# IDC_EXT_Connectors.net
KiCad netlist of a schematic drawn in Altium Designer
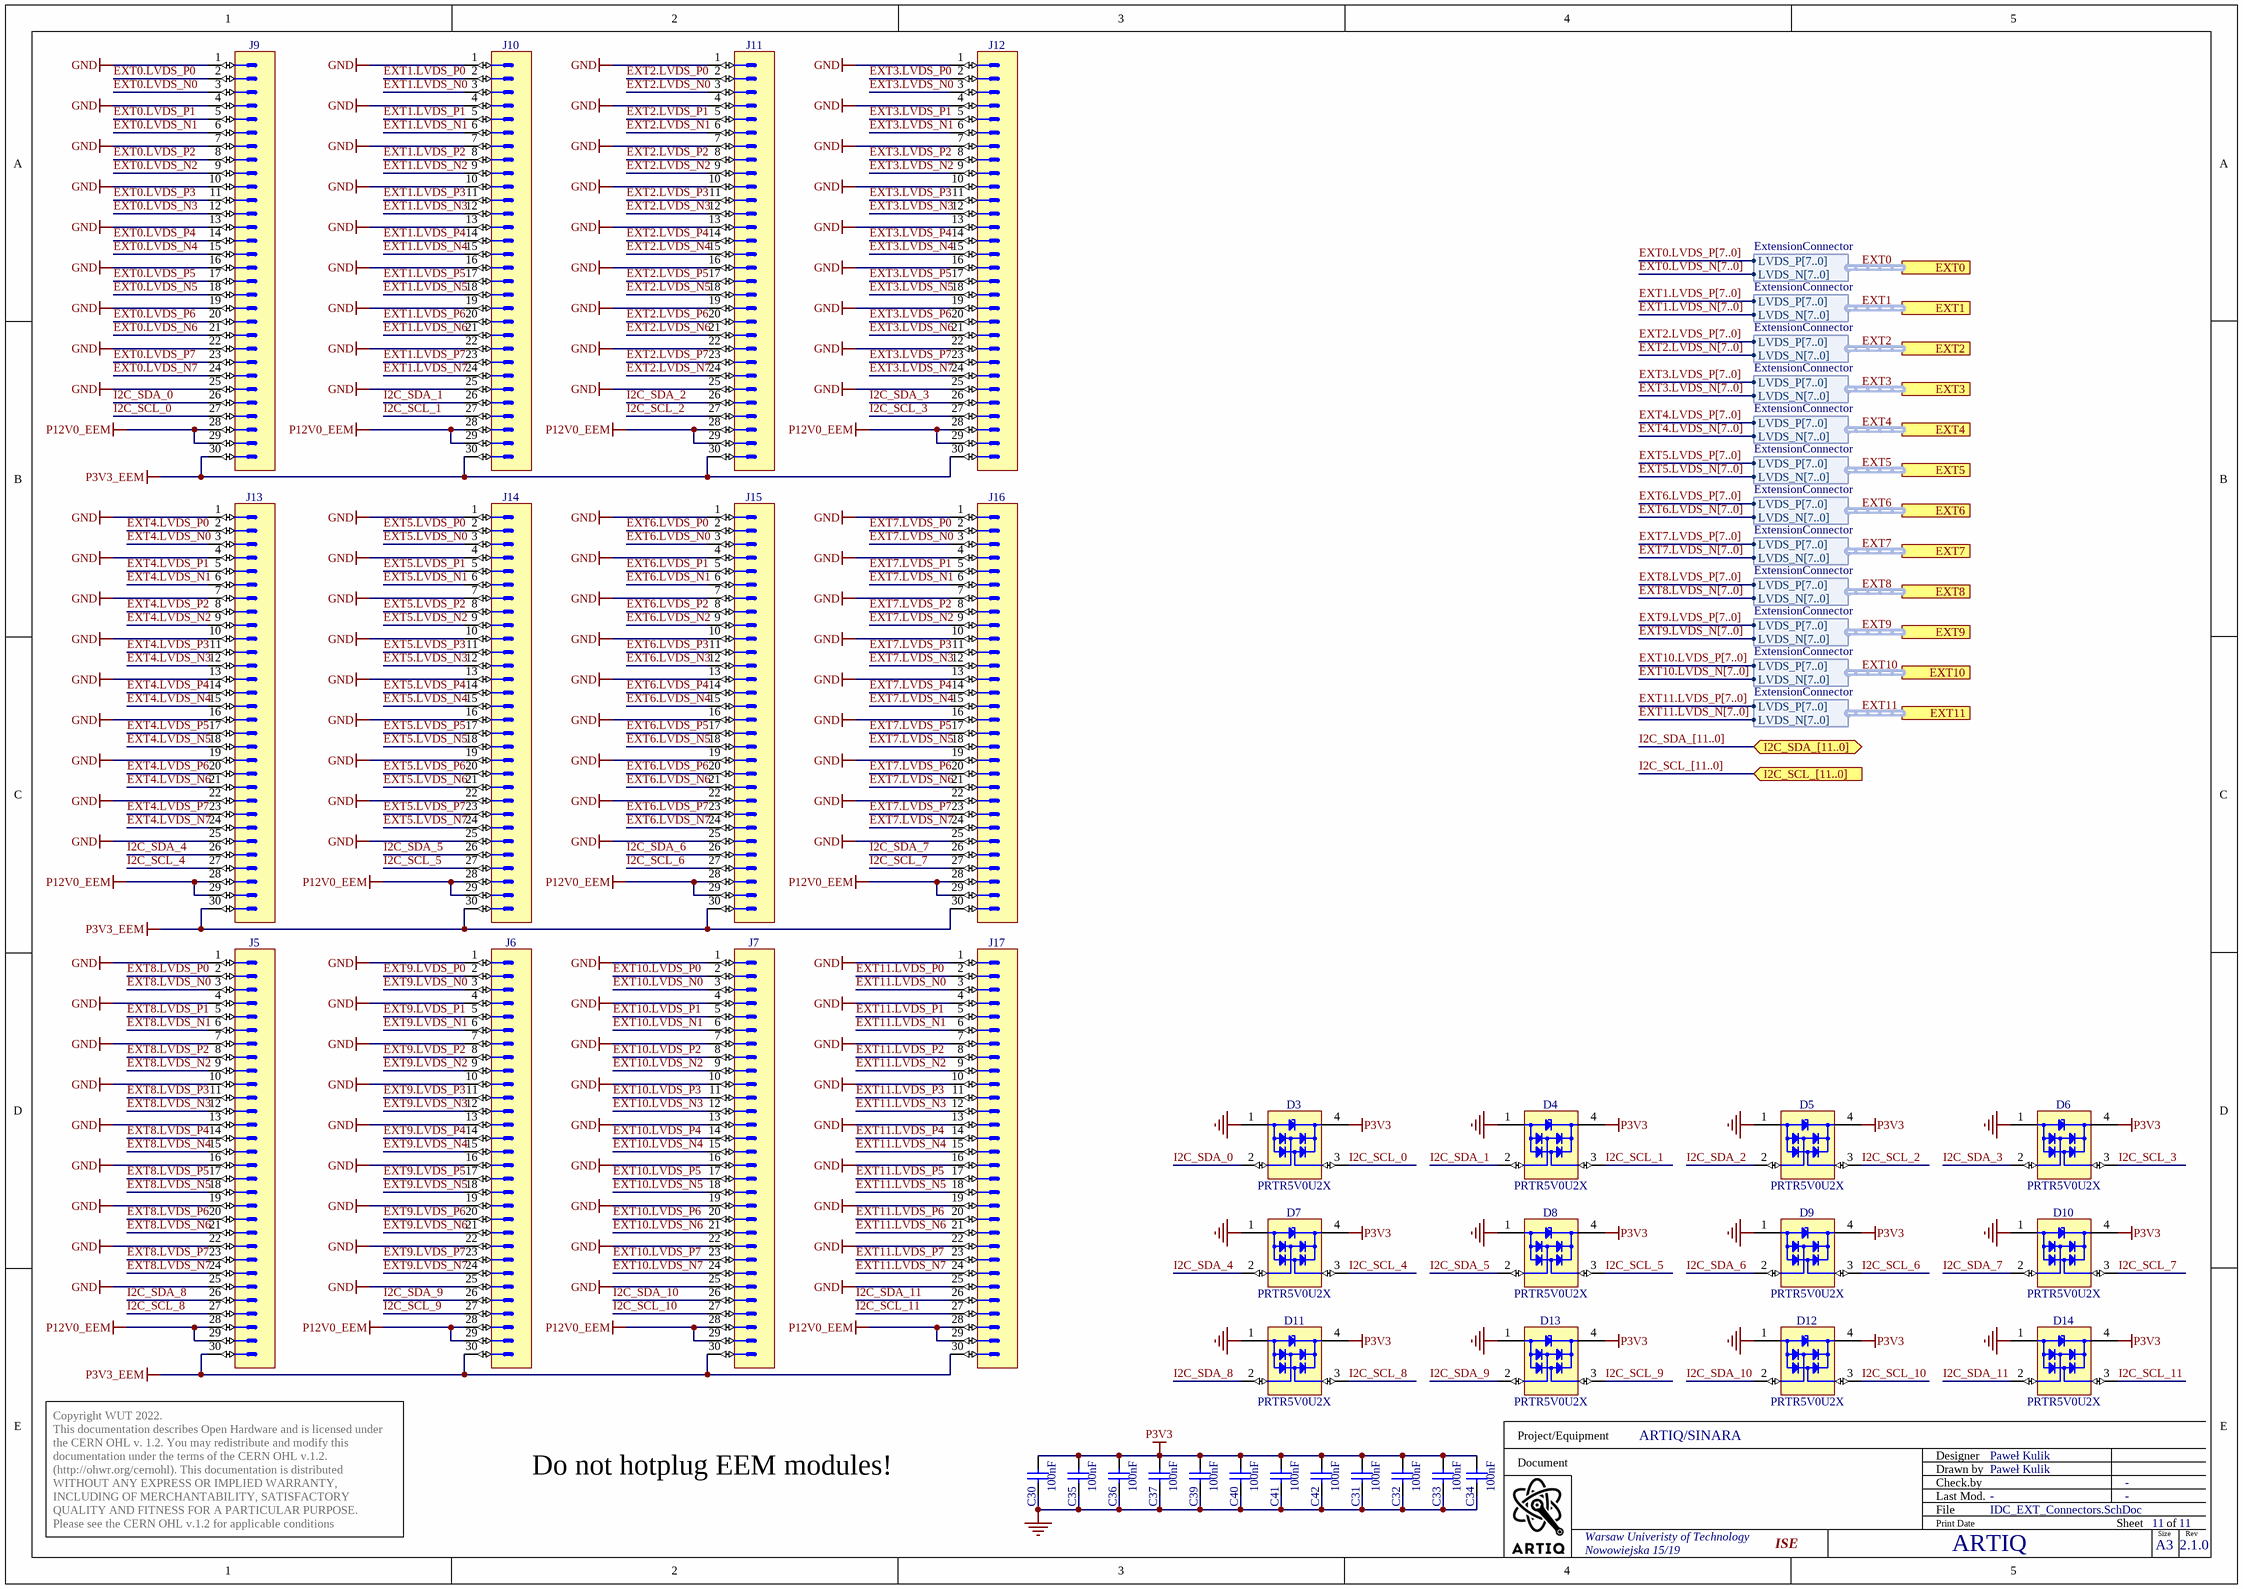
[diagram p0: IDC_EXT_Connectors.SchDoc]

(export (version "E")
  (design (tool "Eeschema 10.0.6"))
  (components
    (comp (ref "C30")
      (value "100nF")
      (footprint "CAPC0603X33N")
      (description "Non-polarised capacitor")
      (fields
        (field (name "PART NUMBER") "CC0201_100NF_6.3V_10%_X5R")
        (field (name "VOLTAGE") "6.3V")
        (field (name "AUTHOR") "CERN DEM JLC")
      )
      (libsource (lib "Capacitors") (part "Capacitor - non polarized"))
    )
    (comp (ref "C31")
      (value "100nF")
      (footprint "CAPC0603X33N")
      (description "Non-polarised capacitor")
      (fields
        (field (name "PART NUMBER") "CC0201_100NF_6.3V_10%_X5R")
        (field (name "VOLTAGE") "6.3V")
        (field (name "AUTHOR") "CERN DEM JLC")
      )
      (libsource (lib "Capacitors") (part "Capacitor - non polarized"))
    )
    (comp (ref "C32")
      (value "100nF")
      (footprint "CAPC0603X33N")
      (description "Non-polarised capacitor")
      (fields
        (field (name "PART NUMBER") "CC0201_100NF_6.3V_10%_X5R")
        (field (name "VOLTAGE") "6.3V")
        (field (name "AUTHOR") "CERN DEM JLC")
      )
      (libsource (lib "Capacitors") (part "Capacitor - non polarized"))
    )
    (comp (ref "C33")
      (value "100nF")
      (footprint "CAPC0603X33N")
      (description "Non-polarised capacitor")
      (fields
        (field (name "PART NUMBER") "CC0201_100NF_6.3V_10%_X5R")
        (field (name "VOLTAGE") "6.3V")
        (field (name "AUTHOR") "CERN DEM JLC")
      )
      (libsource (lib "Capacitors") (part "Capacitor - non polarized"))
    )
    (comp (ref "C34")
      (value "100nF")
      (footprint "CAPC0603X33N")
      (description "Non-polarised capacitor")
      (fields
        (field (name "PART NUMBER") "CC0201_100NF_6.3V_10%_X5R")
        (field (name "VOLTAGE") "6.3V")
        (field (name "AUTHOR") "CERN DEM JLC")
      )
      (libsource (lib "Capacitors") (part "Capacitor - non polarized"))
    )
    (comp (ref "C35")
      (value "100nF")
      (footprint "CAPC0603X33N")
      (description "Non-polarised capacitor")
      (fields
        (field (name "PART NUMBER") "CC0201_100NF_6.3V_10%_X5R")
        (field (name "VOLTAGE") "6.3V")
        (field (name "AUTHOR") "CERN DEM JLC")
      )
      (libsource (lib "Capacitors") (part "Capacitor - non polarized"))
    )
    (comp (ref "C36")
      (value "100nF")
      (footprint "CAPC0603X33N")
      (description "Non-polarised capacitor")
      (fields
        (field (name "PART NUMBER") "CC0201_100NF_6.3V_10%_X5R")
        (field (name "VOLTAGE") "6.3V")
        (field (name "AUTHOR") "CERN DEM JLC")
      )
      (libsource (lib "Capacitors") (part "Capacitor - non polarized"))
    )
    (comp (ref "C37")
      (value "100nF")
      (footprint "CAPC0603X33N")
      (description "Non-polarised capacitor")
      (fields
        (field (name "PART NUMBER") "CC0201_100NF_6.3V_10%_X5R")
        (field (name "VOLTAGE") "6.3V")
        (field (name "AUTHOR") "CERN DEM JLC")
      )
      (libsource (lib "Capacitors") (part "Capacitor - non polarized"))
    )
    (comp (ref "C39")
      (value "100nF")
      (footprint "CAPC0603X33N")
      (description "Non-polarised capacitor")
      (fields
        (field (name "PART NUMBER") "CC0201_100NF_6.3V_10%_X5R")
        (field (name "VOLTAGE") "6.3V")
        (field (name "AUTHOR") "CERN DEM JLC")
      )
      (libsource (lib "Capacitors") (part "Capacitor - non polarized"))
    )
    (comp (ref "C40")
      (value "100nF")
      (footprint "CAPC0603X33N")
      (description "Non-polarised capacitor")
      (fields
        (field (name "PART NUMBER") "CC0201_100NF_6.3V_10%_X5R")
        (field (name "VOLTAGE") "6.3V")
        (field (name "AUTHOR") "CERN DEM JLC")
      )
      (libsource (lib "Capacitors") (part "Capacitor - non polarized"))
    )
    (comp (ref "C41")
      (value "100nF")
      (footprint "CAPC0603X33N")
      (description "Non-polarised capacitor")
      (fields
        (field (name "PART NUMBER") "CC0201_100NF_6.3V_10%_X5R")
        (field (name "VOLTAGE") "6.3V")
        (field (name "AUTHOR") "CERN DEM JLC")
      )
      (libsource (lib "Capacitors") (part "Capacitor - non polarized"))
    )
    (comp (ref "C42")
      (value "100nF")
      (footprint "CAPC0603X33N")
      (description "Non-polarised capacitor")
      (fields
        (field (name "PART NUMBER") "CC0201_100NF_6.3V_10%_X5R")
        (field (name "VOLTAGE") "6.3V")
        (field (name "AUTHOR") "CERN DEM JLC")
      )
      (libsource (lib "Capacitors") (part "Capacitor - non polarized"))
    )
    (comp (ref "D3")
      (value "PRTR5V0U2X")
      (footprint "SOT190P230X110-4N")
      (description "Ultra Low Capacitance Double Rail-to-Rail ESD Protection Diode")
      (fields
        (field (name "VOLTAGE") "5.5V")
        (field (name "MANUFACTURER") "NXP SEMICONDUCTORS")
        (field (name "AUTHOR") "CERN DEM JLC")
      )
      (libsource (lib "ICs And Semiconductors") (part "PRTR5V0U2X"))
    )
    (comp (ref "D4")
      (value "PRTR5V0U2X")
      (footprint "SOT190P230X110-4N")
      (description "Ultra Low Capacitance Double Rail-to-Rail ESD Protection Diode")
      (fields
        (field (name "VOLTAGE") "5.5V")
        (field (name "MANUFACTURER") "NXP SEMICONDUCTORS")
        (field (name "AUTHOR") "CERN DEM JLC")
      )
      (libsource (lib "ICs And Semiconductors") (part "PRTR5V0U2X"))
    )
    (comp (ref "D5")
      (value "PRTR5V0U2X")
      (footprint "SOT190P230X110-4N")
      (description "Ultra Low Capacitance Double Rail-to-Rail ESD Protection Diode")
      (fields
        (field (name "VOLTAGE") "5.5V")
        (field (name "MANUFACTURER") "NXP SEMICONDUCTORS")
        (field (name "AUTHOR") "CERN DEM JLC")
      )
      (libsource (lib "ICs And Semiconductors") (part "PRTR5V0U2X"))
    )
    (comp (ref "D6")
      (value "PRTR5V0U2X")
      (footprint "SOT190P230X110-4N")
      (description "Ultra Low Capacitance Double Rail-to-Rail ESD Protection Diode")
      (fields
        (field (name "VOLTAGE") "5.5V")
        (field (name "MANUFACTURER") "NXP SEMICONDUCTORS")
        (field (name "AUTHOR") "CERN DEM JLC")
      )
      (libsource (lib "ICs And Semiconductors") (part "PRTR5V0U2X"))
    )
    (comp (ref "D7")
      (value "PRTR5V0U2X")
      (footprint "SOT190P230X110-4N")
      (description "Ultra Low Capacitance Double Rail-to-Rail ESD Protection Diode")
      (fields
        (field (name "VOLTAGE") "5.5V")
        (field (name "MANUFACTURER") "NXP SEMICONDUCTORS")
        (field (name "AUTHOR") "CERN DEM JLC")
      )
      (libsource (lib "ICs And Semiconductors") (part "PRTR5V0U2X"))
    )
    (comp (ref "D8")
      (value "PRTR5V0U2X")
      (footprint "SOT190P230X110-4N")
      (description "Ultra Low Capacitance Double Rail-to-Rail ESD Protection Diode")
      (fields
        (field (name "VOLTAGE") "5.5V")
        (field (name "MANUFACTURER") "NXP SEMICONDUCTORS")
        (field (name "AUTHOR") "CERN DEM JLC")
      )
      (libsource (lib "ICs And Semiconductors") (part "PRTR5V0U2X"))
    )
    (comp (ref "D9")
      (value "PRTR5V0U2X")
      (footprint "SOT190P230X110-4N")
      (description "Ultra Low Capacitance Double Rail-to-Rail ESD Protection Diode")
      (fields
        (field (name "VOLTAGE") "5.5V")
        (field (name "MANUFACTURER") "NXP SEMICONDUCTORS")
        (field (name "AUTHOR") "CERN DEM JLC")
      )
      (libsource (lib "ICs And Semiconductors") (part "PRTR5V0U2X"))
    )
    (comp (ref "D10")
      (value "PRTR5V0U2X")
      (footprint "SOT190P230X110-4N")
      (description "Ultra Low Capacitance Double Rail-to-Rail ESD Protection Diode")
      (fields
        (field (name "VOLTAGE") "5.5V")
        (field (name "MANUFACTURER") "NXP SEMICONDUCTORS")
        (field (name "AUTHOR") "CERN DEM JLC")
      )
      (libsource (lib "ICs And Semiconductors") (part "PRTR5V0U2X"))
    )
    (comp (ref "D11")
      (value "PRTR5V0U2X")
      (footprint "SOT190P230X110-4N")
      (description "Ultra Low Capacitance Double Rail-to-Rail ESD Protection Diode")
      (fields
        (field (name "VOLTAGE") "5.5V")
        (field (name "MANUFACTURER") "NXP SEMICONDUCTORS")
        (field (name "AUTHOR") "CERN DEM JLC")
      )
      (libsource (lib "ICs And Semiconductors") (part "PRTR5V0U2X"))
    )
    (comp (ref "D12")
      (value "PRTR5V0U2X")
      (footprint "SOT190P230X110-4N")
      (description "Ultra Low Capacitance Double Rail-to-Rail ESD Protection Diode")
      (fields
        (field (name "VOLTAGE") "5.5V")
        (field (name "MANUFACTURER") "NXP SEMICONDUCTORS")
        (field (name "AUTHOR") "CERN DEM JLC")
      )
      (libsource (lib "ICs And Semiconductors") (part "PRTR5V0U2X"))
    )
    (comp (ref "D13")
      (value "PRTR5V0U2X")
      (footprint "SOT190P230X110-4N")
      (description "Ultra Low Capacitance Double Rail-to-Rail ESD Protection Diode")
      (fields
        (field (name "VOLTAGE") "5.5V")
        (field (name "MANUFACTURER") "NXP SEMICONDUCTORS")
        (field (name "AUTHOR") "CERN DEM JLC")
      )
      (libsource (lib "ICs And Semiconductors") (part "PRTR5V0U2X"))
    )
    (comp (ref "D14")
      (value "PRTR5V0U2X")
      (footprint "SOT190P230X110-4N")
      (description "Ultra Low Capacitance Double Rail-to-Rail ESD Protection Diode")
      (fields
        (field (name "VOLTAGE") "5.5V")
        (field (name "MANUFACTURER") "NXP SEMICONDUCTORS")
        (field (name "AUTHOR") "CERN DEM JLC")
      )
      (libsource (lib "ICs And Semiconductors") (part "PRTR5V0U2X"))
    )
    (comp (ref "J5")
      (value "~")
      (footprint "3M_N2530-6002RB")
      (description "Connector 30 Male")
      (fields
        (field (name "PART NUMBER") "3M_N2530-6002RB")
        (field (name "MANUFACTURER") "3M")
        (field (name "AUTHOR") "CERN DEM JLC")
      )
      (libsource (lib "Connectors") (part "Connector 30 Male"))
    )
    (comp (ref "J6")
      (value "~")
      (footprint "3M_N2530-6002RB")
      (description "Connector 30 Male")
      (fields
        (field (name "PART NUMBER") "3M_N2530-6002RB")
        (field (name "MANUFACTURER") "3M")
        (field (name "AUTHOR") "CERN DEM JLC")
      )
      (libsource (lib "Connectors") (part "Connector 30 Male"))
    )
    (comp (ref "J7")
      (value "~")
      (footprint "3M_N2530-6002RB")
      (description "Connector 30 Male")
      (fields
        (field (name "PART NUMBER") "3M_N2530-6002RB")
        (field (name "MANUFACTURER") "3M")
        (field (name "AUTHOR") "CERN DEM JLC")
      )
      (libsource (lib "Connectors") (part "Connector 30 Male"))
    )
    (comp (ref "J9")
      (value "~")
      (footprint "3M_N2530-6002RB")
      (description "Connector 30 Male")
      (fields
        (field (name "PART NUMBER") "3M_N2530-6002RB")
        (field (name "MANUFACTURER") "3M")
        (field (name "AUTHOR") "CERN DEM JLC")
      )
      (libsource (lib "Connectors") (part "Connector 30 Male"))
    )
    (comp (ref "J10")
      (value "~")
      (footprint "3M_N2530-6002RB")
      (description "Connector 30 Male")
      (fields
        (field (name "PART NUMBER") "3M_N2530-6002RB")
        (field (name "MANUFACTURER") "3M")
        (field (name "AUTHOR") "CERN DEM JLC")
      )
      (libsource (lib "Connectors") (part "Connector 30 Male"))
    )
    (comp (ref "J11")
      (value "~")
      (footprint "3M_N2530-6002RB")
      (description "Connector 30 Male")
      (fields
        (field (name "PART NUMBER") "3M_N2530-6002RB")
        (field (name "MANUFACTURER") "3M")
        (field (name "AUTHOR") "CERN DEM JLC")
      )
      (libsource (lib "Connectors") (part "Connector 30 Male"))
    )
    (comp (ref "J12")
      (value "~")
      (footprint "3M_N2530-6002RB")
      (description "Connector 30 Male")
      (fields
        (field (name "PART NUMBER") "3M_N2530-6002RB")
        (field (name "MANUFACTURER") "3M")
        (field (name "AUTHOR") "CERN DEM JLC")
      )
      (libsource (lib "Connectors") (part "Connector 30 Male"))
    )
    (comp (ref "J13")
      (value "~")
      (footprint "3M_N2530-6002RB")
      (description "Connector 30 Male")
      (fields
        (field (name "PART NUMBER") "3M_N2530-6002RB")
        (field (name "MANUFACTURER") "3M")
        (field (name "AUTHOR") "CERN DEM JLC")
      )
      (libsource (lib "Connectors") (part "Connector 30 Male"))
    )
    (comp (ref "J14")
      (value "~")
      (footprint "3M_N2530-6002RB")
      (description "Connector 30 Male")
      (fields
        (field (name "PART NUMBER") "3M_N2530-6002RB")
        (field (name "MANUFACTURER") "3M")
        (field (name "AUTHOR") "CERN DEM JLC")
      )
      (libsource (lib "Connectors") (part "Connector 30 Male"))
    )
    (comp (ref "J15")
      (value "~")
      (footprint "3M_N2530-6002RB")
      (description "Connector 30 Male")
      (fields
        (field (name "PART NUMBER") "3M_N2530-6002RB")
        (field (name "MANUFACTURER") "3M")
        (field (name "AUTHOR") "CERN DEM JLC")
      )
      (libsource (lib "Connectors") (part "Connector 30 Male"))
    )
    (comp (ref "J16")
      (value "~")
      (footprint "3M_N2530-6002RB")
      (description "Connector 30 Male")
      (fields
        (field (name "PART NUMBER") "3M_N2530-6002RB")
        (field (name "MANUFACTURER") "3M")
        (field (name "AUTHOR") "CERN DEM JLC")
      )
      (libsource (lib "Connectors") (part "Connector 30 Male"))
    )
    (comp (ref "J17")
      (value "~")
      (footprint "3M_N2530-6002RB")
      (description "Connector 30 Male")
      (fields
        (field (name "PART NUMBER") "3M_N2530-6002RB")
        (field (name "MANUFACTURER") "3M")
        (field (name "AUTHOR") "CERN DEM JLC")
      )
      (libsource (lib "Connectors") (part "Connector 30 Male"))
    )
  )
  (nets
    (net (code "13") (name "/EXT0.LVDS_N0") (class "Default")
      (node (ref "J9") (pin "3") (pinfunction "3_3") (pintype "bidirectional"))
    )
    (net (code "14") (name "/EXT0.LVDS_N1") (class "Default")
      (node (ref "J9") (pin "6") (pinfunction "6_6") (pintype "bidirectional"))
    )
    (net (code "15") (name "/EXT0.LVDS_N2") (class "Default")
      (node (ref "J9") (pin "9") (pinfunction "9_9") (pintype "bidirectional"))
    )
    (net (code "16") (name "/EXT0.LVDS_N3") (class "Default")
      (node (ref "J9") (pin "12") (pinfunction "12_12") (pintype "bidirectional"))
    )
    (net (code "17") (name "/EXT0.LVDS_N4") (class "Default")
      (node (ref "J9") (pin "15") (pinfunction "15_15") (pintype "bidirectional"))
    )
    (net (code "18") (name "/EXT0.LVDS_N5") (class "Default")
      (node (ref "J9") (pin "18") (pinfunction "18_18") (pintype "bidirectional"))
    )
    (net (code "19") (name "/EXT0.LVDS_N6") (class "Default")
      (node (ref "J9") (pin "21") (pinfunction "21_21") (pintype "bidirectional"))
    )
    (net (code "20") (name "/EXT0.LVDS_N7") (class "Default")
      (node (ref "J9") (pin "24") (pinfunction "24_24") (pintype "bidirectional"))
    )
    (net (code "21") (name "/EXT0.LVDS_P0") (class "Default")
      (node (ref "J9") (pin "2") (pinfunction "2_2") (pintype "bidirectional"))
    )
    (net (code "22") (name "/EXT0.LVDS_P1") (class "Default")
      (node (ref "J9") (pin "5") (pinfunction "5_5") (pintype "bidirectional"))
    )
    (net (code "23") (name "/EXT0.LVDS_P2") (class "Default")
      (node (ref "J9") (pin "8") (pinfunction "8_8") (pintype "bidirectional"))
    )
    (net (code "24") (name "/EXT0.LVDS_P3") (class "Default")
      (node (ref "J9") (pin "11") (pinfunction "11_11") (pintype "bidirectional"))
    )
    (net (code "25") (name "/EXT0.LVDS_P4") (class "Default")
      (node (ref "J9") (pin "14") (pinfunction "14_14") (pintype "bidirectional"))
    )
    (net (code "26") (name "/EXT0.LVDS_P5") (class "Default")
      (node (ref "J9") (pin "17") (pinfunction "17_17") (pintype "bidirectional"))
    )
    (net (code "27") (name "/EXT0.LVDS_P6") (class "Default")
      (node (ref "J9") (pin "20") (pinfunction "20_20") (pintype "bidirectional"))
    )
    (net (code "28") (name "/EXT0.LVDS_P7") (class "Default")
      (node (ref "J9") (pin "23") (pinfunction "23_23") (pintype "bidirectional"))
    )
    (net (code "30") (name "/EXT1.LVDS_N0") (class "Default")
      (node (ref "J10") (pin "3") (pinfunction "3_3") (pintype "bidirectional"))
    )
    (net (code "31") (name "/EXT1.LVDS_N1") (class "Default")
      (node (ref "J10") (pin "6") (pinfunction "6_6") (pintype "bidirectional"))
    )
    (net (code "32") (name "/EXT1.LVDS_N2") (class "Default")
      (node (ref "J10") (pin "9") (pinfunction "9_9") (pintype "bidirectional"))
    )
    (net (code "33") (name "/EXT1.LVDS_N3") (class "Default")
      (node (ref "J10") (pin "12") (pinfunction "12_12") (pintype "bidirectional"))
    )
    (net (code "34") (name "/EXT1.LVDS_N4") (class "Default")
      (node (ref "J10") (pin "15") (pinfunction "15_15") (pintype "bidirectional"))
    )
    (net (code "35") (name "/EXT1.LVDS_N5") (class "Default")
      (node (ref "J10") (pin "18") (pinfunction "18_18") (pintype "bidirectional"))
    )
    (net (code "36") (name "/EXT1.LVDS_N6") (class "Default")
      (node (ref "J10") (pin "21") (pinfunction "21_21") (pintype "bidirectional"))
    )
    (net (code "37") (name "/EXT1.LVDS_N7") (class "Default")
      (node (ref "J10") (pin "24") (pinfunction "24_24") (pintype "bidirectional"))
    )
    (net (code "39") (name "/EXT1.LVDS_P0") (class "Default")
      (node (ref "J10") (pin "2") (pinfunction "2_2") (pintype "bidirectional"))
    )
    (net (code "40") (name "/EXT1.LVDS_P1") (class "Default")
      (node (ref "J10") (pin "5") (pinfunction "5_5") (pintype "bidirectional"))
    )
    (net (code "41") (name "/EXT1.LVDS_P2") (class "Default")
      (node (ref "J10") (pin "8") (pinfunction "8_8") (pintype "bidirectional"))
    )
    (net (code "42") (name "/EXT1.LVDS_P3") (class "Default")
      (node (ref "J10") (pin "11") (pinfunction "11_11") (pintype "bidirectional"))
    )
    (net (code "43") (name "/EXT1.LVDS_P4") (class "Default")
      (node (ref "J10") (pin "14") (pinfunction "14_14") (pintype "bidirectional"))
    )
    (net (code "44") (name "/EXT1.LVDS_P5") (class "Default")
      (node (ref "J10") (pin "17") (pinfunction "17_17") (pintype "bidirectional"))
    )
    (net (code "45") (name "/EXT1.LVDS_P6") (class "Default")
      (node (ref "J10") (pin "20") (pinfunction "20_20") (pintype "bidirectional"))
    )
    (net (code "46") (name "/EXT1.LVDS_P7") (class "Default")
      (node (ref "J10") (pin "23") (pinfunction "23_23") (pintype "bidirectional"))
    )
    (net (code "49") (name "/EXT2.LVDS_N0") (class "Default")
      (node (ref "J11") (pin "3") (pinfunction "3_3") (pintype "bidirectional"))
    )
    (net (code "50") (name "/EXT2.LVDS_N1") (class "Default")
      (node (ref "J11") (pin "6") (pinfunction "6_6") (pintype "bidirectional"))
    )
    (net (code "51") (name "/EXT2.LVDS_N2") (class "Default")
      (node (ref "J11") (pin "9") (pinfunction "9_9") (pintype "bidirectional"))
    )
    (net (code "52") (name "/EXT2.LVDS_N3") (class "Default")
      (node (ref "J11") (pin "12") (pinfunction "12_12") (pintype "bidirectional"))
    )
    (net (code "53") (name "/EXT2.LVDS_N4") (class "Default")
      (node (ref "J11") (pin "15") (pinfunction "15_15") (pintype "bidirectional"))
    )
    (net (code "54") (name "/EXT2.LVDS_N5") (class "Default")
      (node (ref "J11") (pin "18") (pinfunction "18_18") (pintype "bidirectional"))
    )
    (net (code "55") (name "/EXT2.LVDS_N6") (class "Default")
      (node (ref "J11") (pin "21") (pinfunction "21_21") (pintype "bidirectional"))
    )
    (net (code "56") (name "/EXT2.LVDS_N7") (class "Default")
      (node (ref "J11") (pin "24") (pinfunction "24_24") (pintype "bidirectional"))
    )
    (net (code "58") (name "/EXT2.LVDS_P0") (class "Default")
      (node (ref "J11") (pin "2") (pinfunction "2_2") (pintype "bidirectional"))
    )
    (net (code "59") (name "/EXT2.LVDS_P1") (class "Default")
      (node (ref "J11") (pin "5") (pinfunction "5_5") (pintype "bidirectional"))
    )
    (net (code "60") (name "/EXT2.LVDS_P2") (class "Default")
      (node (ref "J11") (pin "8") (pinfunction "8_8") (pintype "bidirectional"))
    )
    (net (code "61") (name "/EXT2.LVDS_P3") (class "Default")
      (node (ref "J11") (pin "11") (pinfunction "11_11") (pintype "bidirectional"))
    )
    (net (code "62") (name "/EXT2.LVDS_P4") (class "Default")
      (node (ref "J11") (pin "14") (pinfunction "14_14") (pintype "bidirectional"))
    )
    (net (code "63") (name "/EXT2.LVDS_P5") (class "Default")
      (node (ref "J11") (pin "17") (pinfunction "17_17") (pintype "bidirectional"))
    )
    (net (code "64") (name "/EXT2.LVDS_P6") (class "Default")
      (node (ref "J11") (pin "20") (pinfunction "20_20") (pintype "bidirectional"))
    )
    (net (code "65") (name "/EXT2.LVDS_P7") (class "Default")
      (node (ref "J11") (pin "23") (pinfunction "23_23") (pintype "bidirectional"))
    )
    (net (code "68") (name "/EXT3.LVDS_N0") (class "Default")
      (node (ref "J12") (pin "3") (pinfunction "3_3") (pintype "bidirectional"))
    )
    (net (code "69") (name "/EXT3.LVDS_N1") (class "Default")
      (node (ref "J12") (pin "6") (pinfunction "6_6") (pintype "bidirectional"))
    )
    (net (code "70") (name "/EXT3.LVDS_N2") (class "Default")
      (node (ref "J12") (pin "9") (pinfunction "9_9") (pintype "bidirectional"))
    )
    (net (code "71") (name "/EXT3.LVDS_N3") (class "Default")
      (node (ref "J12") (pin "12") (pinfunction "12_12") (pintype "bidirectional"))
    )
    (net (code "72") (name "/EXT3.LVDS_N4") (class "Default")
      (node (ref "J12") (pin "15") (pinfunction "15_15") (pintype "bidirectional"))
    )
    (net (code "73") (name "/EXT3.LVDS_N5") (class "Default")
      (node (ref "J12") (pin "18") (pinfunction "18_18") (pintype "bidirectional"))
    )
    (net (code "74") (name "/EXT3.LVDS_N6") (class "Default")
      (node (ref "J12") (pin "21") (pinfunction "21_21") (pintype "bidirectional"))
    )
    (net (code "75") (name "/EXT3.LVDS_N7") (class "Default")
      (node (ref "J12") (pin "24") (pinfunction "24_24") (pintype "bidirectional"))
    )
    (net (code "77") (name "/EXT3.LVDS_P0") (class "Default")
      (node (ref "J12") (pin "2") (pinfunction "2_2") (pintype "bidirectional"))
    )
    (net (code "78") (name "/EXT3.LVDS_P1") (class "Default")
      (node (ref "J12") (pin "5") (pinfunction "5_5") (pintype "bidirectional"))
    )
    (net (code "79") (name "/EXT3.LVDS_P2") (class "Default")
      (node (ref "J12") (pin "8") (pinfunction "8_8") (pintype "bidirectional"))
    )
    (net (code "80") (name "/EXT3.LVDS_P3") (class "Default")
      (node (ref "J12") (pin "11") (pinfunction "11_11") (pintype "bidirectional"))
    )
    (net (code "81") (name "/EXT3.LVDS_P4") (class "Default")
      (node (ref "J12") (pin "14") (pinfunction "14_14") (pintype "bidirectional"))
    )
    (net (code "82") (name "/EXT3.LVDS_P5") (class "Default")
      (node (ref "J12") (pin "17") (pinfunction "17_17") (pintype "bidirectional"))
    )
    (net (code "83") (name "/EXT3.LVDS_P6") (class "Default")
      (node (ref "J12") (pin "20") (pinfunction "20_20") (pintype "bidirectional"))
    )
    (net (code "84") (name "/EXT3.LVDS_P7") (class "Default")
      (node (ref "J12") (pin "23") (pinfunction "23_23") (pintype "bidirectional"))
    )
    (net (code "85") (name "/EXT4.LVDS_N0") (class "Default")
      (node (ref "J13") (pin "3") (pinfunction "3_3") (pintype "bidirectional"))
    )
    (net (code "86") (name "/EXT4.LVDS_N1") (class "Default")
      (node (ref "J13") (pin "6") (pinfunction "6_6") (pintype "bidirectional"))
    )
    (net (code "87") (name "/EXT4.LVDS_N2") (class "Default")
      (node (ref "J13") (pin "9") (pinfunction "9_9") (pintype "bidirectional"))
    )
    (net (code "88") (name "/EXT4.LVDS_N3") (class "Default")
      (node (ref "J13") (pin "12") (pinfunction "12_12") (pintype "bidirectional"))
    )
    (net (code "89") (name "/EXT4.LVDS_N4") (class "Default")
      (node (ref "J13") (pin "15") (pinfunction "15_15") (pintype "bidirectional"))
    )
    (net (code "90") (name "/EXT4.LVDS_N5") (class "Default")
      (node (ref "J13") (pin "18") (pinfunction "18_18") (pintype "bidirectional"))
    )
    (net (code "91") (name "/EXT4.LVDS_N6") (class "Default")
      (node (ref "J13") (pin "21") (pinfunction "21_21") (pintype "bidirectional"))
    )
    (net (code "92") (name "/EXT4.LVDS_N7") (class "Default")
      (node (ref "J13") (pin "24") (pinfunction "24_24") (pintype "bidirectional"))
    )
    (net (code "93") (name "/EXT4.LVDS_P0") (class "Default")
      (node (ref "J13") (pin "2") (pinfunction "2_2") (pintype "bidirectional"))
    )
    (net (code "94") (name "/EXT4.LVDS_P1") (class "Default")
      (node (ref "J13") (pin "5") (pinfunction "5_5") (pintype "bidirectional"))
    )
    (net (code "95") (name "/EXT4.LVDS_P2") (class "Default")
      (node (ref "J13") (pin "8") (pinfunction "8_8") (pintype "bidirectional"))
    )
    (net (code "96") (name "/EXT4.LVDS_P3") (class "Default")
      (node (ref "J13") (pin "11") (pinfunction "11_11") (pintype "bidirectional"))
    )
    (net (code "97") (name "/EXT4.LVDS_P4") (class "Default")
      (node (ref "J13") (pin "14") (pinfunction "14_14") (pintype "bidirectional"))
    )
    (net (code "98") (name "/EXT4.LVDS_P5") (class "Default")
      (node (ref "J13") (pin "17") (pinfunction "17_17") (pintype "bidirectional"))
    )
    (net (code "99") (name "/EXT4.LVDS_P6") (class "Default")
      (node (ref "J13") (pin "20") (pinfunction "20_20") (pintype "bidirectional"))
    )
    (net (code "100") (name "/EXT4.LVDS_P7") (class "Default")
      (node (ref "J13") (pin "23") (pinfunction "23_23") (pintype "bidirectional"))
    )
    (net (code "102") (name "/EXT5.LVDS_N0") (class "Default")
      (node (ref "J14") (pin "3") (pinfunction "3_3") (pintype "bidirectional"))
    )
    (net (code "103") (name "/EXT5.LVDS_N1") (class "Default")
      (node (ref "J14") (pin "6") (pinfunction "6_6") (pintype "bidirectional"))
    )
    (net (code "104") (name "/EXT5.LVDS_N2") (class "Default")
      (node (ref "J14") (pin "9") (pinfunction "9_9") (pintype "bidirectional"))
    )
    (net (code "105") (name "/EXT5.LVDS_N3") (class "Default")
      (node (ref "J14") (pin "12") (pinfunction "12_12") (pintype "bidirectional"))
    )
    (net (code "106") (name "/EXT5.LVDS_N4") (class "Default")
      (node (ref "J14") (pin "15") (pinfunction "15_15") (pintype "bidirectional"))
    )
    (net (code "107") (name "/EXT5.LVDS_N5") (class "Default")
      (node (ref "J14") (pin "18") (pinfunction "18_18") (pintype "bidirectional"))
    )
    (net (code "108") (name "/EXT5.LVDS_N6") (class "Default")
      (node (ref "J14") (pin "21") (pinfunction "21_21") (pintype "bidirectional"))
    )
    (net (code "109") (name "/EXT5.LVDS_N7") (class "Default")
      (node (ref "J14") (pin "24") (pinfunction "24_24") (pintype "bidirectional"))
    )
    (net (code "111") (name "/EXT5.LVDS_P0") (class "Default")
      (node (ref "J14") (pin "2") (pinfunction "2_2") (pintype "bidirectional"))
    )
    (net (code "112") (name "/EXT5.LVDS_P1") (class "Default")
      (node (ref "J14") (pin "5") (pinfunction "5_5") (pintype "bidirectional"))
    )
    (net (code "113") (name "/EXT5.LVDS_P2") (class "Default")
      (node (ref "J14") (pin "8") (pinfunction "8_8") (pintype "bidirectional"))
    )
    (net (code "114") (name "/EXT5.LVDS_P3") (class "Default")
      (node (ref "J14") (pin "11") (pinfunction "11_11") (pintype "bidirectional"))
    )
    (net (code "115") (name "/EXT5.LVDS_P4") (class "Default")
      (node (ref "J14") (pin "14") (pinfunction "14_14") (pintype "bidirectional"))
    )
    (net (code "116") (name "/EXT5.LVDS_P5") (class "Default")
      (node (ref "J14") (pin "17") (pinfunction "17_17") (pintype "bidirectional"))
    )
    (net (code "117") (name "/EXT5.LVDS_P6") (class "Default")
      (node (ref "J14") (pin "20") (pinfunction "20_20") (pintype "bidirectional"))
    )
    (net (code "118") (name "/EXT5.LVDS_P7") (class "Default")
      (node (ref "J14") (pin "23") (pinfunction "23_23") (pintype "bidirectional"))
    )
    (net (code "119") (name "/EXT6.LVDS_N0") (class "Default")
      (node (ref "J15") (pin "3") (pinfunction "3_3") (pintype "bidirectional"))
    )
    (net (code "120") (name "/EXT6.LVDS_N1") (class "Default")
      (node (ref "J15") (pin "6") (pinfunction "6_6") (pintype "bidirectional"))
    )
    (net (code "121") (name "/EXT6.LVDS_N2") (class "Default")
      (node (ref "J15") (pin "9") (pinfunction "9_9") (pintype "bidirectional"))
    )
    (net (code "122") (name "/EXT6.LVDS_N3") (class "Default")
      (node (ref "J15") (pin "12") (pinfunction "12_12") (pintype "bidirectional"))
    )
    (net (code "123") (name "/EXT6.LVDS_N4") (class "Default")
      (node (ref "J15") (pin "15") (pinfunction "15_15") (pintype "bidirectional"))
    )
    (net (code "124") (name "/EXT6.LVDS_N5") (class "Default")
      (node (ref "J15") (pin "18") (pinfunction "18_18") (pintype "bidirectional"))
    )
    (net (code "125") (name "/EXT6.LVDS_N6") (class "Default")
      (node (ref "J15") (pin "21") (pinfunction "21_21") (pintype "bidirectional"))
    )
    (net (code "126") (name "/EXT6.LVDS_N7") (class "Default")
      (node (ref "J15") (pin "24") (pinfunction "24_24") (pintype "bidirectional"))
    )
    (net (code "127") (name "/EXT6.LVDS_P0") (class "Default")
      (node (ref "J15") (pin "2") (pinfunction "2_2") (pintype "bidirectional"))
    )
    (net (code "128") (name "/EXT6.LVDS_P1") (class "Default")
      (node (ref "J15") (pin "5") (pinfunction "5_5") (pintype "bidirectional"))
    )
    (net (code "129") (name "/EXT6.LVDS_P2") (class "Default")
      (node (ref "J15") (pin "8") (pinfunction "8_8") (pintype "bidirectional"))
    )
    (net (code "130") (name "/EXT6.LVDS_P3") (class "Default")
      (node (ref "J15") (pin "11") (pinfunction "11_11") (pintype "bidirectional"))
    )
    (net (code "131") (name "/EXT6.LVDS_P4") (class "Default")
      (node (ref "J15") (pin "14") (pinfunction "14_14") (pintype "bidirectional"))
    )
    (net (code "132") (name "/EXT6.LVDS_P5") (class "Default")
      (node (ref "J15") (pin "17") (pinfunction "17_17") (pintype "bidirectional"))
    )
    (net (code "133") (name "/EXT6.LVDS_P6") (class "Default")
      (node (ref "J15") (pin "20") (pinfunction "20_20") (pintype "bidirectional"))
    )
    (net (code "134") (name "/EXT6.LVDS_P7") (class "Default")
      (node (ref "J15") (pin "23") (pinfunction "23_23") (pintype "bidirectional"))
    )
    (net (code "136") (name "/EXT7.LVDS_N0") (class "Default")
      (node (ref "J16") (pin "3") (pinfunction "3_3") (pintype "bidirectional"))
    )
    (net (code "137") (name "/EXT7.LVDS_N1") (class "Default")
      (node (ref "J16") (pin "6") (pinfunction "6_6") (pintype "bidirectional"))
    )
    (net (code "138") (name "/EXT7.LVDS_N2") (class "Default")
      (node (ref "J16") (pin "9") (pinfunction "9_9") (pintype "bidirectional"))
    )
    (net (code "139") (name "/EXT7.LVDS_N3") (class "Default")
      (node (ref "J16") (pin "12") (pinfunction "12_12") (pintype "bidirectional"))
    )
    (net (code "140") (name "/EXT7.LVDS_N4") (class "Default")
      (node (ref "J16") (pin "15") (pinfunction "15_15") (pintype "bidirectional"))
    )
    (net (code "141") (name "/EXT7.LVDS_N5") (class "Default")
      (node (ref "J16") (pin "18") (pinfunction "18_18") (pintype "bidirectional"))
    )
    (net (code "142") (name "/EXT7.LVDS_N6") (class "Default")
      (node (ref "J16") (pin "21") (pinfunction "21_21") (pintype "bidirectional"))
    )
    (net (code "143") (name "/EXT7.LVDS_N7") (class "Default")
      (node (ref "J16") (pin "24") (pinfunction "24_24") (pintype "bidirectional"))
    )
    (net (code "144") (name "/EXT7.LVDS_P0") (class "Default")
      (node (ref "J16") (pin "2") (pinfunction "2_2") (pintype "bidirectional"))
    )
    (net (code "145") (name "/EXT7.LVDS_P1") (class "Default")
      (node (ref "J16") (pin "5") (pinfunction "5_5") (pintype "bidirectional"))
    )
    (net (code "146") (name "/EXT7.LVDS_P2") (class "Default")
      (node (ref "J16") (pin "8") (pinfunction "8_8") (pintype "bidirectional"))
    )
    (net (code "147") (name "/EXT7.LVDS_P3") (class "Default")
      (node (ref "J16") (pin "11") (pinfunction "11_11") (pintype "bidirectional"))
    )
    (net (code "148") (name "/EXT7.LVDS_P4") (class "Default")
      (node (ref "J16") (pin "14") (pinfunction "14_14") (pintype "bidirectional"))
    )
    (net (code "149") (name "/EXT7.LVDS_P5") (class "Default")
      (node (ref "J16") (pin "17") (pinfunction "17_17") (pintype "bidirectional"))
    )
    (net (code "150") (name "/EXT7.LVDS_P6") (class "Default")
      (node (ref "J16") (pin "20") (pinfunction "20_20") (pintype "bidirectional"))
    )
    (net (code "151") (name "/EXT7.LVDS_P7") (class "Default")
      (node (ref "J16") (pin "23") (pinfunction "23_23") (pintype "bidirectional"))
    )
    (net (code "153") (name "/EXT8.LVDS_N0") (class "Default")
      (node (ref "J5") (pin "3") (pinfunction "3_3") (pintype "bidirectional"))
    )
    (net (code "154") (name "/EXT8.LVDS_N1") (class "Default")
      (node (ref "J5") (pin "6") (pinfunction "6_6") (pintype "bidirectional"))
    )
    (net (code "155") (name "/EXT8.LVDS_N2") (class "Default")
      (node (ref "J5") (pin "9") (pinfunction "9_9") (pintype "bidirectional"))
    )
    (net (code "156") (name "/EXT8.LVDS_N3") (class "Default")
      (node (ref "J5") (pin "12") (pinfunction "12_12") (pintype "bidirectional"))
    )
    (net (code "157") (name "/EXT8.LVDS_N4") (class "Default")
      (node (ref "J5") (pin "15") (pinfunction "15_15") (pintype "bidirectional"))
    )
    (net (code "158") (name "/EXT8.LVDS_N5") (class "Default")
      (node (ref "J5") (pin "18") (pinfunction "18_18") (pintype "bidirectional"))
    )
    (net (code "159") (name "/EXT8.LVDS_N6") (class "Default")
      (node (ref "J5") (pin "21") (pinfunction "21_21") (pintype "bidirectional"))
    )
    (net (code "160") (name "/EXT8.LVDS_N7") (class "Default")
      (node (ref "J5") (pin "24") (pinfunction "24_24") (pintype "bidirectional"))
    )
    (net (code "162") (name "/EXT8.LVDS_P0") (class "Default")
      (node (ref "J5") (pin "2") (pinfunction "2_2") (pintype "bidirectional"))
    )
    (net (code "163") (name "/EXT8.LVDS_P1") (class "Default")
      (node (ref "J5") (pin "5") (pinfunction "5_5") (pintype "bidirectional"))
    )
    (net (code "164") (name "/EXT8.LVDS_P2") (class "Default")
      (node (ref "J5") (pin "8") (pinfunction "8_8") (pintype "bidirectional"))
    )
    (net (code "165") (name "/EXT8.LVDS_P3") (class "Default")
      (node (ref "J5") (pin "11") (pinfunction "11_11") (pintype "bidirectional"))
    )
    (net (code "166") (name "/EXT8.LVDS_P4") (class "Default")
      (node (ref "J5") (pin "14") (pinfunction "14_14") (pintype "bidirectional"))
    )
    (net (code "167") (name "/EXT8.LVDS_P5") (class "Default")
      (node (ref "J5") (pin "17") (pinfunction "17_17") (pintype "bidirectional"))
    )
    (net (code "168") (name "/EXT8.LVDS_P6") (class "Default")
      (node (ref "J5") (pin "20") (pinfunction "20_20") (pintype "bidirectional"))
    )
    (net (code "169") (name "/EXT8.LVDS_P7") (class "Default")
      (node (ref "J5") (pin "23") (pinfunction "23_23") (pintype "bidirectional"))
    )
    (net (code "172") (name "/EXT9.LVDS_N0") (class "Default")
      (node (ref "J6") (pin "3") (pinfunction "3_3") (pintype "bidirectional"))
    )
    (net (code "173") (name "/EXT9.LVDS_N1") (class "Default")
      (node (ref "J6") (pin "6") (pinfunction "6_6") (pintype "bidirectional"))
    )
    (net (code "174") (name "/EXT9.LVDS_N2") (class "Default")
      (node (ref "J6") (pin "9") (pinfunction "9_9") (pintype "bidirectional"))
    )
    (net (code "175") (name "/EXT9.LVDS_N3") (class "Default")
      (node (ref "J6") (pin "12") (pinfunction "12_12") (pintype "bidirectional"))
    )
    (net (code "176") (name "/EXT9.LVDS_N4") (class "Default")
      (node (ref "J6") (pin "15") (pinfunction "15_15") (pintype "bidirectional"))
    )
    (net (code "177") (name "/EXT9.LVDS_N5") (class "Default")
      (node (ref "J6") (pin "18") (pinfunction "18_18") (pintype "bidirectional"))
    )
    (net (code "178") (name "/EXT9.LVDS_N6") (class "Default")
      (node (ref "J6") (pin "21") (pinfunction "21_21") (pintype "bidirectional"))
    )
    (net (code "179") (name "/EXT9.LVDS_N7") (class "Default")
      (node (ref "J6") (pin "24") (pinfunction "24_24") (pintype "bidirectional"))
    )
    (net (code "181") (name "/EXT9.LVDS_P0") (class "Default")
      (node (ref "J6") (pin "2") (pinfunction "2_2") (pintype "bidirectional"))
    )
    (net (code "182") (name "/EXT9.LVDS_P1") (class "Default")
      (node (ref "J6") (pin "5") (pinfunction "5_5") (pintype "bidirectional"))
    )
    (net (code "183") (name "/EXT9.LVDS_P2") (class "Default")
      (node (ref "J6") (pin "8") (pinfunction "8_8") (pintype "bidirectional"))
    )
    (net (code "184") (name "/EXT9.LVDS_P3") (class "Default")
      (node (ref "J6") (pin "11") (pinfunction "11_11") (pintype "bidirectional"))
    )
    (net (code "185") (name "/EXT9.LVDS_P4") (class "Default")
      (node (ref "J6") (pin "14") (pinfunction "14_14") (pintype "bidirectional"))
    )
    (net (code "186") (name "/EXT9.LVDS_P5") (class "Default")
      (node (ref "J6") (pin "17") (pinfunction "17_17") (pintype "bidirectional"))
    )
    (net (code "187") (name "/EXT9.LVDS_P6") (class "Default")
      (node (ref "J6") (pin "20") (pinfunction "20_20") (pintype "bidirectional"))
    )
    (net (code "188") (name "/EXT9.LVDS_P7") (class "Default")
      (node (ref "J6") (pin "23") (pinfunction "23_23") (pintype "bidirectional"))
    )
    (net (code "191") (name "/EXT10.LVDS_N0") (class "Default")
      (node (ref "J7") (pin "3") (pinfunction "3_3") (pintype "bidirectional"))
    )
    (net (code "192") (name "/EXT10.LVDS_N1") (class "Default")
      (node (ref "J7") (pin "6") (pinfunction "6_6") (pintype "bidirectional"))
    )
    (net (code "193") (name "/EXT10.LVDS_N2") (class "Default")
      (node (ref "J7") (pin "9") (pinfunction "9_9") (pintype "bidirectional"))
    )
    (net (code "194") (name "/EXT10.LVDS_N3") (class "Default")
      (node (ref "J7") (pin "12") (pinfunction "12_12") (pintype "bidirectional"))
    )
    (net (code "195") (name "/EXT10.LVDS_N4") (class "Default")
      (node (ref "J7") (pin "15") (pinfunction "15_15") (pintype "bidirectional"))
    )
    (net (code "196") (name "/EXT10.LVDS_N5") (class "Default")
      (node (ref "J7") (pin "18") (pinfunction "18_18") (pintype "bidirectional"))
    )
    (net (code "197") (name "/EXT10.LVDS_N6") (class "Default")
      (node (ref "J7") (pin "21") (pinfunction "21_21") (pintype "bidirectional"))
    )
    (net (code "198") (name "/EXT10.LVDS_N7") (class "Default")
      (node (ref "J7") (pin "24") (pinfunction "24_24") (pintype "bidirectional"))
    )
    (net (code "200") (name "/EXT10.LVDS_P0") (class "Default")
      (node (ref "J7") (pin "2") (pinfunction "2_2") (pintype "bidirectional"))
    )
    (net (code "201") (name "/EXT10.LVDS_P1") (class "Default")
      (node (ref "J7") (pin "5") (pinfunction "5_5") (pintype "bidirectional"))
    )
    (net (code "202") (name "/EXT10.LVDS_P2") (class "Default")
      (node (ref "J7") (pin "8") (pinfunction "8_8") (pintype "bidirectional"))
    )
    (net (code "203") (name "/EXT10.LVDS_P3") (class "Default")
      (node (ref "J7") (pin "11") (pinfunction "11_11") (pintype "bidirectional"))
    )
    (net (code "204") (name "/EXT10.LVDS_P4") (class "Default")
      (node (ref "J7") (pin "14") (pinfunction "14_14") (pintype "bidirectional"))
    )
    (net (code "205") (name "/EXT10.LVDS_P5") (class "Default")
      (node (ref "J7") (pin "17") (pinfunction "17_17") (pintype "bidirectional"))
    )
    (net (code "206") (name "/EXT10.LVDS_P6") (class "Default")
      (node (ref "J7") (pin "20") (pinfunction "20_20") (pintype "bidirectional"))
    )
    (net (code "207") (name "/EXT10.LVDS_P7") (class "Default")
      (node (ref "J7") (pin "23") (pinfunction "23_23") (pintype "bidirectional"))
    )
    (net (code "210") (name "/EXT11.LVDS_N0") (class "Default")
      (node (ref "J17") (pin "3") (pinfunction "3_3") (pintype "bidirectional"))
    )
    (net (code "211") (name "/EXT11.LVDS_N1") (class "Default")
      (node (ref "J17") (pin "6") (pinfunction "6_6") (pintype "bidirectional"))
    )
    (net (code "212") (name "/EXT11.LVDS_N2") (class "Default")
      (node (ref "J17") (pin "9") (pinfunction "9_9") (pintype "bidirectional"))
    )
    (net (code "213") (name "/EXT11.LVDS_N3") (class "Default")
      (node (ref "J17") (pin "12") (pinfunction "12_12") (pintype "bidirectional"))
    )
    (net (code "214") (name "/EXT11.LVDS_N4") (class "Default")
      (node (ref "J17") (pin "15") (pinfunction "15_15") (pintype "bidirectional"))
    )
    (net (code "215") (name "/EXT11.LVDS_N5") (class "Default")
      (node (ref "J17") (pin "18") (pinfunction "18_18") (pintype "bidirectional"))
    )
    (net (code "216") (name "/EXT11.LVDS_N6") (class "Default")
      (node (ref "J17") (pin "21") (pinfunction "21_21") (pintype "bidirectional"))
    )
    (net (code "217") (name "/EXT11.LVDS_N7") (class "Default")
      (node (ref "J17") (pin "24") (pinfunction "24_24") (pintype "bidirectional"))
    )
    (net (code "219") (name "/EXT11.LVDS_P0") (class "Default")
      (node (ref "J17") (pin "2") (pinfunction "2_2") (pintype "bidirectional"))
    )
    (net (code "220") (name "/EXT11.LVDS_P1") (class "Default")
      (node (ref "J17") (pin "5") (pinfunction "5_5") (pintype "bidirectional"))
    )
    (net (code "221") (name "/EXT11.LVDS_P2") (class "Default")
      (node (ref "J17") (pin "8") (pinfunction "8_8") (pintype "bidirectional"))
    )
    (net (code "222") (name "/EXT11.LVDS_P3") (class "Default")
      (node (ref "J17") (pin "11") (pinfunction "11_11") (pintype "bidirectional"))
    )
    (net (code "223") (name "/EXT11.LVDS_P4") (class "Default")
      (node (ref "J17") (pin "14") (pinfunction "14_14") (pintype "bidirectional"))
    )
    (net (code "224") (name "/EXT11.LVDS_P5") (class "Default")
      (node (ref "J17") (pin "17") (pinfunction "17_17") (pintype "bidirectional"))
    )
    (net (code "225") (name "/EXT11.LVDS_P6") (class "Default")
      (node (ref "J17") (pin "20") (pinfunction "20_20") (pintype "bidirectional"))
    )
    (net (code "226") (name "/EXT11.LVDS_P7") (class "Default")
      (node (ref "J17") (pin "23") (pinfunction "23_23") (pintype "bidirectional"))
    )
    (net (code "229") (name "/I2C_SCL_0") (class "Default")
      (node (ref "D3") (pin "3") (pinfunction "I/O2_3") (pintype "bidirectional"))
      (node (ref "J9") (pin "27") (pinfunction "27_27") (pintype "bidirectional"))
    )
    (net (code "230") (name "/I2C_SCL_1") (class "Default")
      (node (ref "D4") (pin "3") (pinfunction "I/O2_3") (pintype "bidirectional"))
      (node (ref "J10") (pin "27") (pinfunction "27_27") (pintype "bidirectional"))
    )
    (net (code "231") (name "/I2C_SCL_2") (class "Default")
      (node (ref "D5") (pin "3") (pinfunction "I/O2_3") (pintype "bidirectional"))
      (node (ref "J11") (pin "27") (pinfunction "27_27") (pintype "bidirectional"))
    )
    (net (code "232") (name "/I2C_SCL_3") (class "Default")
      (node (ref "D6") (pin "3") (pinfunction "I/O2_3") (pintype "bidirectional"))
      (node (ref "J12") (pin "27") (pinfunction "27_27") (pintype "bidirectional"))
    )
    (net (code "233") (name "/I2C_SCL_4") (class "Default")
      (node (ref "D7") (pin "3") (pinfunction "I/O2_3") (pintype "bidirectional"))
      (node (ref "J13") (pin "27") (pinfunction "27_27") (pintype "bidirectional"))
    )
    (net (code "234") (name "/I2C_SCL_5") (class "Default")
      (node (ref "D8") (pin "3") (pinfunction "I/O2_3") (pintype "bidirectional"))
      (node (ref "J14") (pin "27") (pinfunction "27_27") (pintype "bidirectional"))
    )
    (net (code "235") (name "/I2C_SCL_6") (class "Default")
      (node (ref "D9") (pin "3") (pinfunction "I/O2_3") (pintype "bidirectional"))
      (node (ref "J15") (pin "27") (pinfunction "27_27") (pintype "bidirectional"))
    )
    (net (code "236") (name "/I2C_SCL_7") (class "Default")
      (node (ref "D10") (pin "3") (pinfunction "I/O2_3") (pintype "bidirectional"))
      (node (ref "J16") (pin "27") (pinfunction "27_27") (pintype "bidirectional"))
    )
    (net (code "237") (name "/I2C_SCL_8") (class "Default")
      (node (ref "D11") (pin "3") (pinfunction "I/O2_3") (pintype "bidirectional"))
      (node (ref "J5") (pin "27") (pinfunction "27_27") (pintype "bidirectional"))
    )
    (net (code "238") (name "/I2C_SCL_9") (class "Default")
      (node (ref "D13") (pin "3") (pinfunction "I/O2_3") (pintype "bidirectional"))
      (node (ref "J6") (pin "27") (pinfunction "27_27") (pintype "bidirectional"))
    )
    (net (code "239") (name "/I2C_SCL_10") (class "Default")
      (node (ref "D12") (pin "3") (pinfunction "I/O2_3") (pintype "bidirectional"))
      (node (ref "J7") (pin "27") (pinfunction "27_27") (pintype "bidirectional"))
    )
    (net (code "240") (name "/I2C_SCL_11") (class "Default")
      (node (ref "D14") (pin "3") (pinfunction "I/O2_3") (pintype "bidirectional"))
      (node (ref "J17") (pin "27") (pinfunction "27_27") (pintype "bidirectional"))
    )
    (net (code "242") (name "/I2C_SDA_0") (class "Default")
      (node (ref "D3") (pin "2") (pinfunction "I/O1_2") (pintype "bidirectional"))
      (node (ref "J9") (pin "26") (pinfunction "26_26") (pintype "bidirectional"))
    )
    (net (code "243") (name "/I2C_SDA_1") (class "Default")
      (node (ref "D4") (pin "2") (pinfunction "I/O1_2") (pintype "bidirectional"))
      (node (ref "J10") (pin "26") (pinfunction "26_26") (pintype "bidirectional"))
    )
    (net (code "244") (name "/I2C_SDA_2") (class "Default")
      (node (ref "D5") (pin "2") (pinfunction "I/O1_2") (pintype "bidirectional"))
      (node (ref "J11") (pin "26") (pinfunction "26_26") (pintype "bidirectional"))
    )
    (net (code "245") (name "/I2C_SDA_3") (class "Default")
      (node (ref "D6") (pin "2") (pinfunction "I/O1_2") (pintype "bidirectional"))
      (node (ref "J12") (pin "26") (pinfunction "26_26") (pintype "bidirectional"))
    )
    (net (code "246") (name "/I2C_SDA_4") (class "Default")
      (node (ref "D7") (pin "2") (pinfunction "I/O1_2") (pintype "bidirectional"))
      (node (ref "J13") (pin "26") (pinfunction "26_26") (pintype "bidirectional"))
    )
    (net (code "247") (name "/I2C_SDA_5") (class "Default")
      (node (ref "D8") (pin "2") (pinfunction "I/O1_2") (pintype "bidirectional"))
      (node (ref "J14") (pin "26") (pinfunction "26_26") (pintype "bidirectional"))
    )
    (net (code "248") (name "/I2C_SDA_6") (class "Default")
      (node (ref "D9") (pin "2") (pinfunction "I/O1_2") (pintype "bidirectional"))
      (node (ref "J15") (pin "26") (pinfunction "26_26") (pintype "bidirectional"))
    )
    (net (code "249") (name "/I2C_SDA_7") (class "Default")
      (node (ref "D10") (pin "2") (pinfunction "I/O1_2") (pintype "bidirectional"))
      (node (ref "J16") (pin "26") (pinfunction "26_26") (pintype "bidirectional"))
    )
    (net (code "250") (name "/I2C_SDA_8") (class "Default")
      (node (ref "D11") (pin "2") (pinfunction "I/O1_2") (pintype "bidirectional"))
      (node (ref "J5") (pin "26") (pinfunction "26_26") (pintype "bidirectional"))
    )
    (net (code "251") (name "/I2C_SDA_9") (class "Default")
      (node (ref "D13") (pin "2") (pinfunction "I/O1_2") (pintype "bidirectional"))
      (node (ref "J6") (pin "26") (pinfunction "26_26") (pintype "bidirectional"))
    )
    (net (code "252") (name "/I2C_SDA_10") (class "Default")
      (node (ref "D12") (pin "2") (pinfunction "I/O1_2") (pintype "bidirectional"))
      (node (ref "J7") (pin "26") (pinfunction "26_26") (pintype "bidirectional"))
    )
    (net (code "253") (name "/I2C_SDA_11") (class "Default")
      (node (ref "D14") (pin "2") (pinfunction "I/O1_2") (pintype "bidirectional"))
      (node (ref "J17") (pin "26") (pinfunction "26_26") (pintype "bidirectional"))
    )
    (net (code "263") (name "GND") (class "Default")
      (node (ref "C30") (pin "1") (pinfunction "1_1") (pintype "passive"))
      (node (ref "C31") (pin "1") (pinfunction "1_1") (pintype "passive"))
      (node (ref "C32") (pin "1") (pinfunction "1_1") (pintype "passive"))
      (node (ref "C33") (pin "1") (pinfunction "1_1") (pintype "passive"))
      (node (ref "C34") (pin "1") (pinfunction "1_1") (pintype "passive"))
      (node (ref "C35") (pin "1") (pinfunction "1_1") (pintype "passive"))
      (node (ref "C36") (pin "1") (pinfunction "1_1") (pintype "passive"))
      (node (ref "C37") (pin "1") (pinfunction "1_1") (pintype "passive"))
      (node (ref "C39") (pin "1") (pinfunction "1_1") (pintype "passive"))
      (node (ref "C40") (pin "1") (pinfunction "1_1") (pintype "passive"))
      (node (ref "C41") (pin "1") (pinfunction "1_1") (pintype "passive"))
      (node (ref "C42") (pin "1") (pinfunction "1_1") (pintype "passive"))
      (node (ref "D10") (pin "1") (pinfunction "GND_1") (pintype "power_in"))
      (node (ref "D11") (pin "1") (pinfunction "GND_1") (pintype "power_in"))
      (node (ref "D12") (pin "1") (pinfunction "GND_1") (pintype "power_in"))
      (node (ref "D13") (pin "1") (pinfunction "GND_1") (pintype "power_in"))
      (node (ref "D14") (pin "1") (pinfunction "GND_1") (pintype "power_in"))
      (node (ref "D3") (pin "1") (pinfunction "GND_1") (pintype "power_in"))
      (node (ref "D4") (pin "1") (pinfunction "GND_1") (pintype "power_in"))
      (node (ref "D5") (pin "1") (pinfunction "GND_1") (pintype "power_in"))
      (node (ref "D6") (pin "1") (pinfunction "GND_1") (pintype "power_in"))
      (node (ref "D7") (pin "1") (pinfunction "GND_1") (pintype "power_in"))
      (node (ref "D8") (pin "1") (pinfunction "GND_1") (pintype "power_in"))
      (node (ref "D9") (pin "1") (pinfunction "GND_1") (pintype "power_in"))
      (node (ref "J10") (pin "1") (pinfunction "1_1") (pintype "bidirectional"))
      (node (ref "J10") (pin "10") (pinfunction "10_10") (pintype "bidirectional"))
      (node (ref "J10") (pin "13") (pinfunction "13_13") (pintype "bidirectional"))
      (node (ref "J10") (pin "16") (pinfunction "16_16") (pintype "bidirectional"))
      (node (ref "J10") (pin "19") (pinfunction "19_19") (pintype "bidirectional"))
      (node (ref "J10") (pin "22") (pinfunction "22_22") (pintype "bidirectional"))
      (node (ref "J10") (pin "25") (pinfunction "25_25") (pintype "bidirectional"))
      (node (ref "J10") (pin "4") (pinfunction "4_4") (pintype "bidirectional"))
      (node (ref "J10") (pin "7") (pinfunction "7_7") (pintype "bidirectional"))
      (node (ref "J11") (pin "1") (pinfunction "1_1") (pintype "bidirectional"))
      (node (ref "J11") (pin "10") (pinfunction "10_10") (pintype "bidirectional"))
      (node (ref "J11") (pin "13") (pinfunction "13_13") (pintype "bidirectional"))
      (node (ref "J11") (pin "16") (pinfunction "16_16") (pintype "bidirectional"))
      (node (ref "J11") (pin "19") (pinfunction "19_19") (pintype "bidirectional"))
      (node (ref "J11") (pin "22") (pinfunction "22_22") (pintype "bidirectional"))
      (node (ref "J11") (pin "25") (pinfunction "25_25") (pintype "bidirectional"))
      (node (ref "J11") (pin "4") (pinfunction "4_4") (pintype "bidirectional"))
      (node (ref "J11") (pin "7") (pinfunction "7_7") (pintype "bidirectional"))
      (node (ref "J12") (pin "1") (pinfunction "1_1") (pintype "bidirectional"))
      (node (ref "J12") (pin "10") (pinfunction "10_10") (pintype "bidirectional"))
      (node (ref "J12") (pin "13") (pinfunction "13_13") (pintype "bidirectional"))
      (node (ref "J12") (pin "16") (pinfunction "16_16") (pintype "bidirectional"))
      (node (ref "J12") (pin "19") (pinfunction "19_19") (pintype "bidirectional"))
      (node (ref "J12") (pin "22") (pinfunction "22_22") (pintype "bidirectional"))
      (node (ref "J12") (pin "25") (pinfunction "25_25") (pintype "bidirectional"))
      (node (ref "J12") (pin "4") (pinfunction "4_4") (pintype "bidirectional"))
      (node (ref "J12") (pin "7") (pinfunction "7_7") (pintype "bidirectional"))
      (node (ref "J13") (pin "1") (pinfunction "1_1") (pintype "bidirectional"))
      (node (ref "J13") (pin "10") (pinfunction "10_10") (pintype "bidirectional"))
      (node (ref "J13") (pin "13") (pinfunction "13_13") (pintype "bidirectional"))
      (node (ref "J13") (pin "16") (pinfunction "16_16") (pintype "bidirectional"))
      (node (ref "J13") (pin "19") (pinfunction "19_19") (pintype "bidirectional"))
      (node (ref "J13") (pin "22") (pinfunction "22_22") (pintype "bidirectional"))
      (node (ref "J13") (pin "25") (pinfunction "25_25") (pintype "bidirectional"))
      (node (ref "J13") (pin "4") (pinfunction "4_4") (pintype "bidirectional"))
      (node (ref "J13") (pin "7") (pinfunction "7_7") (pintype "bidirectional"))
      (node (ref "J14") (pin "1") (pinfunction "1_1") (pintype "bidirectional"))
      (node (ref "J14") (pin "10") (pinfunction "10_10") (pintype "bidirectional"))
      (node (ref "J14") (pin "13") (pinfunction "13_13") (pintype "bidirectional"))
      (node (ref "J14") (pin "16") (pinfunction "16_16") (pintype "bidirectional"))
      (node (ref "J14") (pin "19") (pinfunction "19_19") (pintype "bidirectional"))
      (node (ref "J14") (pin "22") (pinfunction "22_22") (pintype "bidirectional"))
      (node (ref "J14") (pin "25") (pinfunction "25_25") (pintype "bidirectional"))
      (node (ref "J14") (pin "4") (pinfunction "4_4") (pintype "bidirectional"))
      (node (ref "J14") (pin "7") (pinfunction "7_7") (pintype "bidirectional"))
      (node (ref "J15") (pin "1") (pinfunction "1_1") (pintype "bidirectional"))
      (node (ref "J15") (pin "10") (pinfunction "10_10") (pintype "bidirectional"))
      (node (ref "J15") (pin "13") (pinfunction "13_13") (pintype "bidirectional"))
      (node (ref "J15") (pin "16") (pinfunction "16_16") (pintype "bidirectional"))
      (node (ref "J15") (pin "19") (pinfunction "19_19") (pintype "bidirectional"))
      (node (ref "J15") (pin "22") (pinfunction "22_22") (pintype "bidirectional"))
      (node (ref "J15") (pin "25") (pinfunction "25_25") (pintype "bidirectional"))
      (node (ref "J15") (pin "4") (pinfunction "4_4") (pintype "bidirectional"))
      (node (ref "J15") (pin "7") (pinfunction "7_7") (pintype "bidirectional"))
      (node (ref "J16") (pin "1") (pinfunction "1_1") (pintype "bidirectional"))
      (node (ref "J16") (pin "10") (pinfunction "10_10") (pintype "bidirectional"))
      (node (ref "J16") (pin "13") (pinfunction "13_13") (pintype "bidirectional"))
      (node (ref "J16") (pin "16") (pinfunction "16_16") (pintype "bidirectional"))
      (node (ref "J16") (pin "19") (pinfunction "19_19") (pintype "bidirectional"))
      (node (ref "J16") (pin "22") (pinfunction "22_22") (pintype "bidirectional"))
      (node (ref "J16") (pin "25") (pinfunction "25_25") (pintype "bidirectional"))
      (node (ref "J16") (pin "4") (pinfunction "4_4") (pintype "bidirectional"))
      (node (ref "J16") (pin "7") (pinfunction "7_7") (pintype "bidirectional"))
      (node (ref "J17") (pin "1") (pinfunction "1_1") (pintype "bidirectional"))
      (node (ref "J17") (pin "10") (pinfunction "10_10") (pintype "bidirectional"))
      (node (ref "J17") (pin "13") (pinfunction "13_13") (pintype "bidirectional"))
      (node (ref "J17") (pin "16") (pinfunction "16_16") (pintype "bidirectional"))
      (node (ref "J17") (pin "19") (pinfunction "19_19") (pintype "bidirectional"))
      (node (ref "J17") (pin "22") (pinfunction "22_22") (pintype "bidirectional"))
      (node (ref "J17") (pin "25") (pinfunction "25_25") (pintype "bidirectional"))
      (node (ref "J17") (pin "4") (pinfunction "4_4") (pintype "bidirectional"))
      (node (ref "J17") (pin "7") (pinfunction "7_7") (pintype "bidirectional"))
      (node (ref "J5") (pin "1") (pinfunction "1_1") (pintype "bidirectional"))
      (node (ref "J5") (pin "10") (pinfunction "10_10") (pintype "bidirectional"))
      (node (ref "J5") (pin "13") (pinfunction "13_13") (pintype "bidirectional"))
      (node (ref "J5") (pin "16") (pinfunction "16_16") (pintype "bidirectional"))
      (node (ref "J5") (pin "19") (pinfunction "19_19") (pintype "bidirectional"))
      (node (ref "J5") (pin "22") (pinfunction "22_22") (pintype "bidirectional"))
      (node (ref "J5") (pin "25") (pinfunction "25_25") (pintype "bidirectional"))
      (node (ref "J5") (pin "4") (pinfunction "4_4") (pintype "bidirectional"))
      (node (ref "J5") (pin "7") (pinfunction "7_7") (pintype "bidirectional"))
      (node (ref "J6") (pin "1") (pinfunction "1_1") (pintype "bidirectional"))
      (node (ref "J6") (pin "10") (pinfunction "10_10") (pintype "bidirectional"))
      (node (ref "J6") (pin "13") (pinfunction "13_13") (pintype "bidirectional"))
      (node (ref "J6") (pin "16") (pinfunction "16_16") (pintype "bidirectional"))
      (node (ref "J6") (pin "19") (pinfunction "19_19") (pintype "bidirectional"))
      (node (ref "J6") (pin "22") (pinfunction "22_22") (pintype "bidirectional"))
      (node (ref "J6") (pin "25") (pinfunction "25_25") (pintype "bidirectional"))
      (node (ref "J6") (pin "4") (pinfunction "4_4") (pintype "bidirectional"))
      (node (ref "J6") (pin "7") (pinfunction "7_7") (pintype "bidirectional"))
      (node (ref "J7") (pin "1") (pinfunction "1_1") (pintype "bidirectional"))
      (node (ref "J7") (pin "10") (pinfunction "10_10") (pintype "bidirectional"))
      (node (ref "J7") (pin "13") (pinfunction "13_13") (pintype "bidirectional"))
      (node (ref "J7") (pin "16") (pinfunction "16_16") (pintype "bidirectional"))
      (node (ref "J7") (pin "19") (pinfunction "19_19") (pintype "bidirectional"))
      (node (ref "J7") (pin "22") (pinfunction "22_22") (pintype "bidirectional"))
      (node (ref "J7") (pin "25") (pinfunction "25_25") (pintype "bidirectional"))
      (node (ref "J7") (pin "4") (pinfunction "4_4") (pintype "bidirectional"))
      (node (ref "J7") (pin "7") (pinfunction "7_7") (pintype "bidirectional"))
      (node (ref "J9") (pin "1") (pinfunction "1_1") (pintype "bidirectional"))
      (node (ref "J9") (pin "10") (pinfunction "10_10") (pintype "bidirectional"))
      (node (ref "J9") (pin "13") (pinfunction "13_13") (pintype "bidirectional"))
      (node (ref "J9") (pin "16") (pinfunction "16_16") (pintype "bidirectional"))
      (node (ref "J9") (pin "19") (pinfunction "19_19") (pintype "bidirectional"))
      (node (ref "J9") (pin "22") (pinfunction "22_22") (pintype "bidirectional"))
      (node (ref "J9") (pin "25") (pinfunction "25_25") (pintype "bidirectional"))
      (node (ref "J9") (pin "4") (pinfunction "4_4") (pintype "bidirectional"))
      (node (ref "J9") (pin "7") (pinfunction "7_7") (pintype "bidirectional"))
    )
    (net (code "264") (name "P3V3") (class "Default")
      (node (ref "C30") (pin "2") (pinfunction "2_2") (pintype "passive"))
      (node (ref "C31") (pin "2") (pinfunction "2_2") (pintype "passive"))
      (node (ref "C32") (pin "2") (pinfunction "2_2") (pintype "passive"))
      (node (ref "C33") (pin "2") (pinfunction "2_2") (pintype "passive"))
      (node (ref "C34") (pin "2") (pinfunction "2_2") (pintype "passive"))
      (node (ref "C35") (pin "2") (pinfunction "2_2") (pintype "passive"))
      (node (ref "C36") (pin "2") (pinfunction "2_2") (pintype "passive"))
      (node (ref "C37") (pin "2") (pinfunction "2_2") (pintype "passive"))
      (node (ref "C39") (pin "2") (pinfunction "2_2") (pintype "passive"))
      (node (ref "C40") (pin "2") (pinfunction "2_2") (pintype "passive"))
      (node (ref "C41") (pin "2") (pinfunction "2_2") (pintype "passive"))
      (node (ref "C42") (pin "2") (pinfunction "2_2") (pintype "passive"))
      (node (ref "D10") (pin "4") (pinfunction "VCC_4") (pintype "power_in"))
      (node (ref "D11") (pin "4") (pinfunction "VCC_4") (pintype "power_in"))
      (node (ref "D12") (pin "4") (pinfunction "VCC_4") (pintype "power_in"))
      (node (ref "D13") (pin "4") (pinfunction "VCC_4") (pintype "power_in"))
      (node (ref "D14") (pin "4") (pinfunction "VCC_4") (pintype "power_in"))
      (node (ref "D3") (pin "4") (pinfunction "VCC_4") (pintype "power_in"))
      (node (ref "D4") (pin "4") (pinfunction "VCC_4") (pintype "power_in"))
      (node (ref "D5") (pin "4") (pinfunction "VCC_4") (pintype "power_in"))
      (node (ref "D6") (pin "4") (pinfunction "VCC_4") (pintype "power_in"))
      (node (ref "D7") (pin "4") (pinfunction "VCC_4") (pintype "power_in"))
      (node (ref "D8") (pin "4") (pinfunction "VCC_4") (pintype "power_in"))
      (node (ref "D9") (pin "4") (pinfunction "VCC_4") (pintype "power_in"))
    )
    (net (code "265") (name "P3V3_EEM") (class "Default")
      (node (ref "J10") (pin "30") (pinfunction "30_30") (pintype "bidirectional"))
      (node (ref "J11") (pin "30") (pinfunction "30_30") (pintype "bidirectional"))
      (node (ref "J12") (pin "30") (pinfunction "30_30") (pintype "bidirectional"))
      (node (ref "J13") (pin "30") (pinfunction "30_30") (pintype "bidirectional"))
      (node (ref "J14") (pin "30") (pinfunction "30_30") (pintype "bidirectional"))
      (node (ref "J15") (pin "30") (pinfunction "30_30") (pintype "bidirectional"))
      (node (ref "J16") (pin "30") (pinfunction "30_30") (pintype "bidirectional"))
      (node (ref "J17") (pin "30") (pinfunction "30_30") (pintype "bidirectional"))
      (node (ref "J5") (pin "30") (pinfunction "30_30") (pintype "bidirectional"))
      (node (ref "J6") (pin "30") (pinfunction "30_30") (pintype "bidirectional"))
      (node (ref "J7") (pin "30") (pinfunction "30_30") (pintype "bidirectional"))
      (node (ref "J9") (pin "30") (pinfunction "30_30") (pintype "bidirectional"))
    )
    (net (code "266") (name "P12V0_EEM") (class "Default")
      (node (ref "J10") (pin "28") (pinfunction "28_28") (pintype "bidirectional"))
      (node (ref "J10") (pin "29") (pinfunction "29_29") (pintype "bidirectional"))
      (node (ref "J11") (pin "28") (pinfunction "28_28") (pintype "bidirectional"))
      (node (ref "J11") (pin "29") (pinfunction "29_29") (pintype "bidirectional"))
      (node (ref "J12") (pin "28") (pinfunction "28_28") (pintype "bidirectional"))
      (node (ref "J12") (pin "29") (pinfunction "29_29") (pintype "bidirectional"))
      (node (ref "J13") (pin "28") (pinfunction "28_28") (pintype "bidirectional"))
      (node (ref "J13") (pin "29") (pinfunction "29_29") (pintype "bidirectional"))
      (node (ref "J14") (pin "28") (pinfunction "28_28") (pintype "bidirectional"))
      (node (ref "J14") (pin "29") (pinfunction "29_29") (pintype "bidirectional"))
      (node (ref "J15") (pin "28") (pinfunction "28_28") (pintype "bidirectional"))
      (node (ref "J15") (pin "29") (pinfunction "29_29") (pintype "bidirectional"))
      (node (ref "J16") (pin "28") (pinfunction "28_28") (pintype "bidirectional"))
      (node (ref "J16") (pin "29") (pinfunction "29_29") (pintype "bidirectional"))
      (node (ref "J17") (pin "28") (pinfunction "28_28") (pintype "bidirectional"))
      (node (ref "J17") (pin "29") (pinfunction "29_29") (pintype "bidirectional"))
      (node (ref "J5") (pin "28") (pinfunction "28_28") (pintype "bidirectional"))
      (node (ref "J5") (pin "29") (pinfunction "29_29") (pintype "bidirectional"))
      (node (ref "J6") (pin "28") (pinfunction "28_28") (pintype "bidirectional"))
      (node (ref "J6") (pin "29") (pinfunction "29_29") (pintype "bidirectional"))
      (node (ref "J7") (pin "28") (pinfunction "28_28") (pintype "bidirectional"))
      (node (ref "J7") (pin "29") (pinfunction "29_29") (pintype "bidirectional"))
      (node (ref "J9") (pin "28") (pinfunction "28_28") (pintype "bidirectional"))
      (node (ref "J9") (pin "29") (pinfunction "29_29") (pintype "bidirectional"))
    )
  )
)
